# MODUL_RASP-PI_BRIDGE_V100.net
KiCad netlist of a schematic drawn in EAGLE
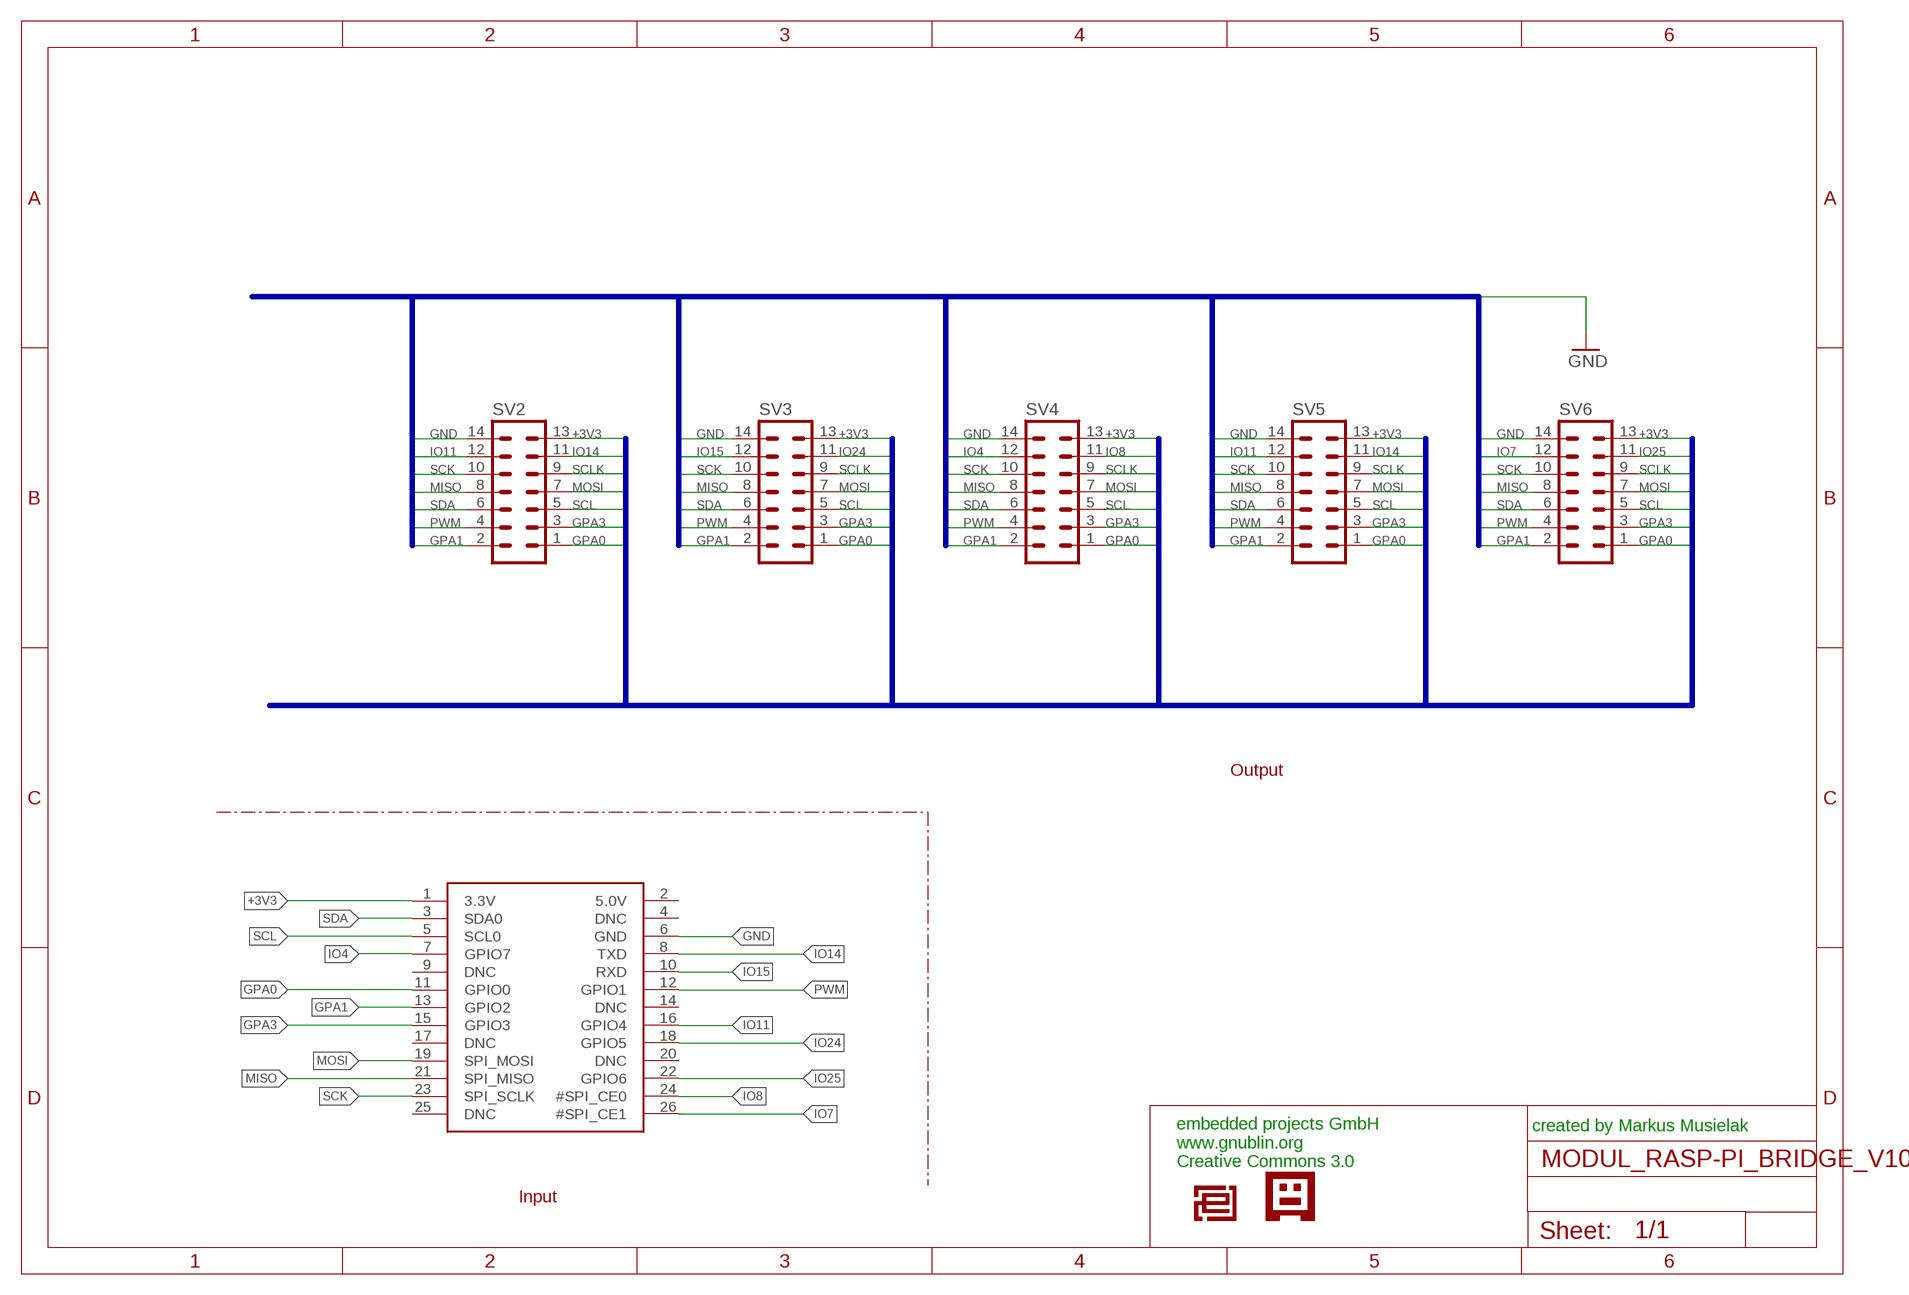
[diagram p0: schematic, sheet 1]

(export (version "E")
  (design (tool "Eeschema 10.0.6"))
  (components
    (comp (ref "SV2")
      (value "ML14")
      (footprint "eagle-import:ML14")
      (libsource (lib "eagle-import") (part "ML14"))
    )
    (comp (ref "SV3")
      (value "ML14")
      (footprint "eagle-import:ML14")
      (libsource (lib "eagle-import") (part "ML14"))
    )
    (comp (ref "SV4")
      (value "ML14")
      (footprint "eagle-import:ML14")
      (libsource (lib "eagle-import") (part "ML14"))
    )
    (comp (ref "SV5")
      (value "ML14")
      (footprint "eagle-import:ML14")
      (libsource (lib "eagle-import") (part "ML14"))
    )
    (comp (ref "SV6")
      (value "ML14")
      (footprint "eagle-import:ML14")
      (libsource (lib "eagle-import") (part "ML14"))
    )
    (comp (ref "U$1")
      (value "RASPBERRYPI_BB")
      (footprint "eagle-import:RASBERRYPI_SHIELD")
      (libsource (lib "eagle-import") (part "RASPBERRYPI_BB"))
    )
    (comp (ref "U$2")
      (value "EPLOGOSIEB")
      (footprint "eagle-import:EPLOGOSIEBDRUCK")
      (libsource (lib "eagle-import") (part "EPLOGOSIEB"))
    )
    (comp (ref "U$4")
      (value "GNUBLINLOGOSIEB")
      (footprint "eagle-import:GNUSIEBDRUCK")
      (libsource (lib "eagle-import") (part "GNUBLINLOGOSIEB"))
    )
  )
  (nets
    (net (code "1") (name "+3V3") (class "Default")
      (node (ref "SV2") (pin "13") (pinfunction "13_13") (pintype "passive"))
      (node (ref "SV3") (pin "13") (pinfunction "13_13") (pintype "passive"))
      (node (ref "SV4") (pin "13") (pinfunction "13_13") (pintype "passive"))
      (node (ref "SV5") (pin "13") (pinfunction "13_13") (pintype "passive"))
      (node (ref "SV6") (pin "13") (pinfunction "13_13") (pintype "passive"))
      (node (ref "U$1") (pin "1") (pinfunction "3.3V_1") (pintype "power_in"))
    )
    (net (code "2") (name "/5.0V") (class "Default")
      (node (ref "U$1") (pin "2") (pinfunction "5.0V_2") (pintype "power_in"))
    )
    (net (code "3") (name "/SCLK") (class "Default")
      (node (ref "SV2") (pin "9") (pinfunction "9_9") (pintype "passive"))
      (node (ref "SV3") (pin "9") (pinfunction "9_9") (pintype "passive"))
      (node (ref "SV4") (pin "9") (pinfunction "9_9") (pintype "passive"))
      (node (ref "SV5") (pin "9") (pinfunction "9_9") (pintype "passive"))
      (node (ref "SV6") (pin "9") (pinfunction "9_9") (pintype "passive"))
    )
    (net (code "4") (name "GND") (class "Default")
      (node (ref "SV2") (pin "14") (pinfunction "14_14") (pintype "passive"))
      (node (ref "SV3") (pin "14") (pinfunction "14_14") (pintype "passive"))
      (node (ref "SV4") (pin "14") (pinfunction "14_14") (pintype "passive"))
      (node (ref "SV5") (pin "14") (pinfunction "14_14") (pintype "passive"))
      (node (ref "SV6") (pin "14") (pinfunction "14_14") (pintype "passive"))
      (node (ref "U$1") (pin "6") (pinfunction "GND_6") (pintype "power_in"))
    )
    (net (code "5") (name "GPA0") (class "Default")
      (node (ref "SV2") (pin "1") (pinfunction "1_1") (pintype "passive"))
      (node (ref "SV3") (pin "1") (pinfunction "1_1") (pintype "passive"))
      (node (ref "SV4") (pin "1") (pinfunction "1_1") (pintype "passive"))
      (node (ref "SV5") (pin "1") (pinfunction "1_1") (pintype "passive"))
      (node (ref "SV6") (pin "1") (pinfunction "1_1") (pintype "passive"))
      (node (ref "U$1") (pin "11") (pinfunction "GPIO0_11") (pintype "bidirectional"))
    )
    (net (code "6") (name "GPA1") (class "Default")
      (node (ref "SV2") (pin "2") (pinfunction "2_2") (pintype "passive"))
      (node (ref "SV3") (pin "2") (pinfunction "2_2") (pintype "passive"))
      (node (ref "SV4") (pin "2") (pinfunction "2_2") (pintype "passive"))
      (node (ref "SV5") (pin "2") (pinfunction "2_2") (pintype "passive"))
      (node (ref "SV6") (pin "2") (pinfunction "2_2") (pintype "passive"))
      (node (ref "U$1") (pin "13") (pinfunction "GPIO2_13") (pintype "bidirectional"))
    )
    (net (code "7") (name "GPA3") (class "Default")
      (node (ref "SV2") (pin "3") (pinfunction "3_3") (pintype "passive"))
      (node (ref "SV3") (pin "3") (pinfunction "3_3") (pintype "passive"))
      (node (ref "SV4") (pin "3") (pinfunction "3_3") (pintype "passive"))
      (node (ref "SV5") (pin "3") (pinfunction "3_3") (pintype "passive"))
      (node (ref "SV6") (pin "3") (pinfunction "3_3") (pintype "passive"))
      (node (ref "U$1") (pin "15") (pinfunction "GPIO3_15") (pintype "bidirectional"))
    )
    (net (code "8") (name "IO4") (class "Default")
      (node (ref "SV4") (pin "12") (pinfunction "12_12") (pintype "passive"))
      (node (ref "U$1") (pin "7") (pinfunction "GPIO7_7") (pintype "bidirectional"))
    )
    (net (code "9") (name "IO7") (class "Default")
      (node (ref "SV6") (pin "12") (pinfunction "12_12") (pintype "passive"))
      (node (ref "U$1") (pin "26") (pinfunction "#SPI_CE1_26") (pintype "output"))
    )
    (net (code "10") (name "IO8") (class "Default")
      (node (ref "SV4") (pin "11") (pinfunction "11_11") (pintype "passive"))
      (node (ref "U$1") (pin "24") (pinfunction "#SPI_CE0_24") (pintype "output"))
    )
    (net (code "11") (name "IO11") (class "Default")
      (node (ref "SV2") (pin "12") (pinfunction "12_12") (pintype "passive"))
      (node (ref "SV5") (pin "12") (pinfunction "12_12") (pintype "passive"))
      (node (ref "U$1") (pin "16") (pinfunction "GPIO4_16") (pintype "bidirectional"))
    )
    (net (code "12") (name "IO14") (class "Default")
      (node (ref "SV2") (pin "11") (pinfunction "11_11") (pintype "passive"))
      (node (ref "SV5") (pin "11") (pinfunction "11_11") (pintype "passive"))
      (node (ref "U$1") (pin "8") (pinfunction "TXD_8") (pintype "output"))
    )
    (net (code "13") (name "IO15") (class "Default")
      (node (ref "SV3") (pin "12") (pinfunction "12_12") (pintype "passive"))
      (node (ref "U$1") (pin "10") (pinfunction "RXD_10") (pintype "input"))
    )
    (net (code "14") (name "IO24") (class "Default")
      (node (ref "SV3") (pin "11") (pinfunction "11_11") (pintype "passive"))
      (node (ref "U$1") (pin "18") (pinfunction "GPIO5_18") (pintype "bidirectional"))
    )
    (net (code "15") (name "IO25") (class "Default")
      (node (ref "SV6") (pin "11") (pinfunction "11_11") (pintype "passive"))
      (node (ref "U$1") (pin "22") (pinfunction "GPIO6_22") (pintype "bidirectional"))
    )
    (net (code "16") (name "MISO") (class "Default")
      (node (ref "SV2") (pin "8") (pinfunction "8_8") (pintype "passive"))
      (node (ref "SV3") (pin "8") (pinfunction "8_8") (pintype "passive"))
      (node (ref "SV4") (pin "8") (pinfunction "8_8") (pintype "passive"))
      (node (ref "SV5") (pin "8") (pinfunction "8_8") (pintype "passive"))
      (node (ref "SV6") (pin "8") (pinfunction "8_8") (pintype "passive"))
      (node (ref "U$1") (pin "21") (pinfunction "SPI_MISO_21") (pintype "input"))
    )
    (net (code "17") (name "MOSI") (class "Default")
      (node (ref "SV2") (pin "7") (pinfunction "7_7") (pintype "passive"))
      (node (ref "SV3") (pin "7") (pinfunction "7_7") (pintype "passive"))
      (node (ref "SV4") (pin "7") (pinfunction "7_7") (pintype "passive"))
      (node (ref "SV5") (pin "7") (pinfunction "7_7") (pintype "passive"))
      (node (ref "SV6") (pin "7") (pinfunction "7_7") (pintype "passive"))
      (node (ref "U$1") (pin "19") (pinfunction "SPI_MOSI_19") (pintype "output"))
    )
    (net (code "18") (name "PWM") (class "Default")
      (node (ref "SV2") (pin "4") (pinfunction "4_4") (pintype "passive"))
      (node (ref "SV3") (pin "4") (pinfunction "4_4") (pintype "passive"))
      (node (ref "SV4") (pin "4") (pinfunction "4_4") (pintype "passive"))
      (node (ref "SV5") (pin "4") (pinfunction "4_4") (pintype "passive"))
      (node (ref "SV6") (pin "4") (pinfunction "4_4") (pintype "passive"))
      (node (ref "U$1") (pin "12") (pinfunction "GPIO1_12") (pintype "bidirectional"))
    )
    (net (code "19") (name "SCK") (class "Default")
      (node (ref "SV2") (pin "10") (pinfunction "10_10") (pintype "passive"))
      (node (ref "SV3") (pin "10") (pinfunction "10_10") (pintype "passive"))
      (node (ref "SV4") (pin "10") (pinfunction "10_10") (pintype "passive"))
      (node (ref "SV5") (pin "10") (pinfunction "10_10") (pintype "passive"))
      (node (ref "SV6") (pin "10") (pinfunction "10_10") (pintype "passive"))
      (node (ref "U$1") (pin "23") (pinfunction "SPI_SCLK_23") (pintype "output"))
    )
    (net (code "20") (name "SCL") (class "Default")
      (node (ref "SV2") (pin "5") (pinfunction "5_5") (pintype "passive"))
      (node (ref "SV3") (pin "5") (pinfunction "5_5") (pintype "passive"))
      (node (ref "SV4") (pin "5") (pinfunction "5_5") (pintype "passive"))
      (node (ref "SV5") (pin "5") (pinfunction "5_5") (pintype "passive"))
      (node (ref "SV6") (pin "5") (pinfunction "5_5") (pintype "passive"))
      (node (ref "U$1") (pin "5") (pinfunction "SCL0_5") (pintype "output"))
    )
    (net (code "21") (name "SDA") (class "Default")
      (node (ref "SV2") (pin "6") (pinfunction "6_6") (pintype "passive"))
      (node (ref "SV3") (pin "6") (pinfunction "6_6") (pintype "passive"))
      (node (ref "SV4") (pin "6") (pinfunction "6_6") (pintype "passive"))
      (node (ref "SV5") (pin "6") (pinfunction "6_6") (pintype "passive"))
      (node (ref "SV6") (pin "6") (pinfunction "6_6") (pintype "passive"))
      (node (ref "U$1") (pin "3") (pinfunction "SDA0_3") (pintype "bidirectional"))
    )
    (net (code "22") (name "unconnected-(U$1-DNC-Pad4)") (class "Default")
      (node (ref "U$1") (pin "4") (pinfunction "DNC_4") (pintype "no_connect"))
    )
    (net (code "23") (name "unconnected-(U$1-DNC-Pad9)") (class "Default")
      (node (ref "U$1") (pin "9") (pinfunction "DNC_9") (pintype "no_connect"))
    )
    (net (code "24") (name "unconnected-(U$1-DNC-Pad14)") (class "Default")
      (node (ref "U$1") (pin "14") (pinfunction "DNC_14") (pintype "no_connect"))
    )
    (net (code "25") (name "unconnected-(U$1-DNC-Pad17)") (class "Default")
      (node (ref "U$1") (pin "17") (pinfunction "DNC_17") (pintype "no_connect"))
    )
    (net (code "26") (name "unconnected-(U$1-DNC-Pad20)") (class "Default")
      (node (ref "U$1") (pin "20") (pinfunction "DNC_20") (pintype "no_connect"))
    )
    (net (code "27") (name "unconnected-(U$1-DNC-Pad25)") (class "Default")
      (node (ref "U$1") (pin "25") (pinfunction "DNC_25") (pintype "no_connect"))
    )
  )
)
